# sch_microcontroller.net
KiCad netlist of a schematic drawn in EasyEDA
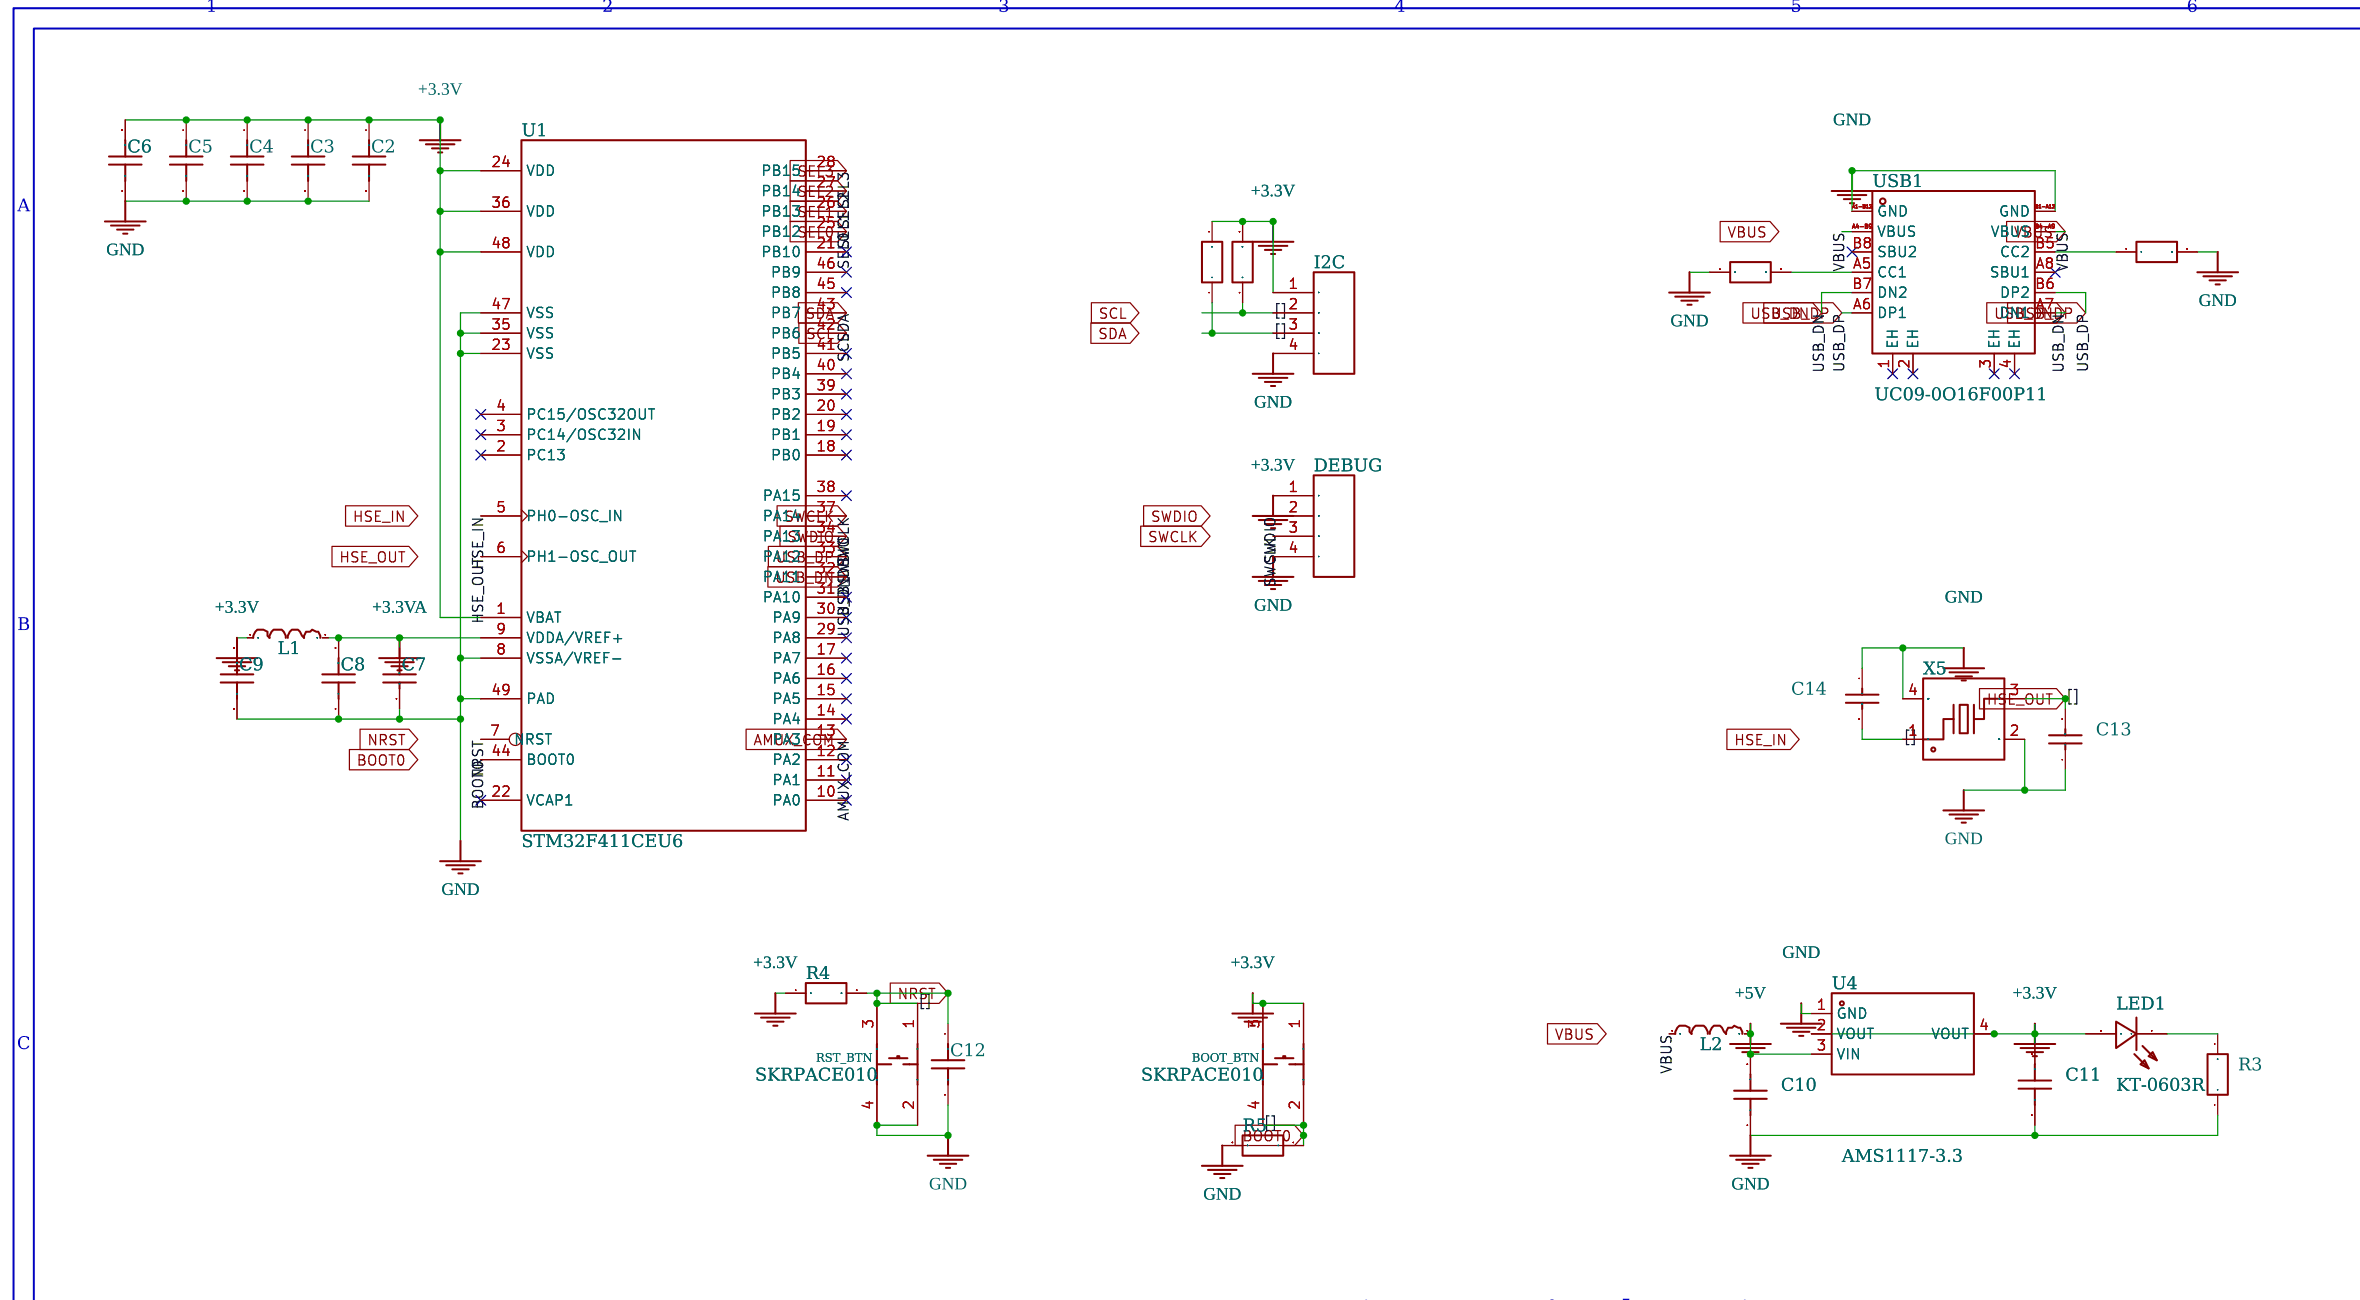
[diagram p0: schematic sheet]

(export (version "E")
  (design (tool "Eeschema 10.0.6"))
  (components
    (comp (ref "BOOT_BTN")
      (value "SKRPACE010")
      (fields (field (name "Manufacturer") "ALPSALPINE(阿尔卑斯阿尔派)"))
      (libsource (lib "") (part "Unknown_650_-325"))
    )
    (comp (ref "C2")
      (value "100nF")
      (fields
        (field (name "Manufacturer Part") "TCC0201X7R104K160ZT")
        (field (name "Manufacturer") "CCTC(三环)")
      )
      (libsource (lib "") (part "Unknown_195_-770"))
    )
    (comp (ref "C3")
      (value "100nF")
      (fields
        (field (name "Manufacturer Part") "TCC0201X7R104K160ZT")
        (field (name "Manufacturer") "CCTC(三环)")
      )
      (libsource (lib "") (part "Unknown_165_-770"))
    )
    (comp (ref "C4")
      (value "100nF")
      (fields
        (field (name "Manufacturer Part") "TCC0201X7R104K160ZT")
        (field (name "Manufacturer") "CCTC(三环)")
      )
      (libsource (lib "") (part "Unknown_135_-770"))
    )
    (comp (ref "C5")
      (value "100nF")
      (fields
        (field (name "Manufacturer Part") "TCC0201X7R104K160ZT")
        (field (name "Manufacturer") "CCTC(三环)")
      )
      (libsource (lib "") (part "Unknown_105_-770"))
    )
    (comp (ref "C6")
      (value "10uF")
      (fields
        (field (name "Manufacturer Part") "HGC1206R7106K350NSPJ")
        (field (name "Manufacturer") "Chinocera(华瓷)")
      )
      (libsource (lib "") (part "Unknown_75_-770"))
    )
    (comp (ref "C7")
      (value "10nF")
      (fields (field (name "Manufacturer Part") "0402B103K500NT") (field (name "Manufacturer") "FH(风华)"))
      (libsource (lib "") (part "Unknown_210_-515"))
    )
    (comp (ref "C8")
      (value "1uF")
      (fields
        (field (name "Manufacturer Part") "TCC0402X5R105K500AT")
        (field (name "Manufacturer") "CCTC(三环)")
      )
      (libsource (lib "") (part "Unknown_180_-515"))
    )
    (comp (ref "C9")
      (value "1uF")
      (fields
        (field (name "Manufacturer Part") "TCC0402X5R105K500AT")
        (field (name "Manufacturer") "CCTC(三环)")
      )
      (libsource (lib "") (part "Unknown_130_-515"))
    )
    (comp (ref "C10")
      (value "22uF")
      (fields
        (field (name "Manufacturer Part") "TCC1206X7R226K160HT")
        (field (name "Manufacturer") "CCTC(三环)")
      )
      (libsource (lib "") (part "Unknown_875_-310"))
    )
    (comp (ref "C11")
      (value "22uF")
      (fields
        (field (name "Manufacturer Part") "TCC1206X7R226K160HT")
        (field (name "Manufacturer") "CCTC(三环)")
      )
      (libsource (lib "") (part "Unknown_1015_-315"))
    )
    (comp (ref "C12")
      (value "100nF")
      (fields
        (field (name "Manufacturer Part") "TCC0201X7R104K160ZT")
        (field (name "Manufacturer") "CCTC(三环)")
      )
      (libsource (lib "") (part "Unknown_480_-325"))
    )
    (comp (ref "C13")
      (value "20pF")
      (fields (field (name "Manufacturer Part") "0402CG200J500NT") (field (name "Manufacturer") "FH(风华)"))
      (libsource (lib "") (part "Unknown_1030_-485"))
    )
    (comp (ref "C14")
      (value "20pF")
      (fields (field (name "Manufacturer Part") "0402CG200J500NT") (field (name "Manufacturer") "FH(风华)"))
      (libsource (lib "") (part "Unknown_930_-505"))
    )
    (comp (ref "DEBUG") (value "NO") (libsource (lib "") (part "Unknown_640_-595")))
    (comp (ref "I2C") (value "NO") (libsource (lib "") (part "Unknown_640_-695")))
    (comp (ref "L1")
      (value "BLM18AG121SN1D")
      (fields (field (name "Manufacturer") "muRata(村田)"))
      (libsource (lib "") (part "Unknown_155_-535"))
    )
    (comp (ref "L2")
      (value "BLM18AG121SN1D")
      (fields (field (name "Manufacturer") "muRata(村田)"))
      (libsource (lib "") (part "Unknown_855_-340"))
    )
    (comp (ref "LED1")
      (value "KT-0603R")
      (fields (field (name "Manufacturer") "KENTO"))
      (libsource (lib "") (part "Unknown_1060_-340"))
    )
    (comp (ref "R1")
      (value "5.1kΩ")
      (fields (field (name "Manufacturer Part") "FRC0402J512 TS") (field (name "Manufacturer") "FOJAN(富捷)"))
      (libsource (lib "") (part "Unknown_875_-715"))
    )
    (comp (ref "R2")
      (value "5.1kΩ")
      (fields (field (name "Manufacturer Part") "FRC0402J512 TS") (field (name "Manufacturer") "FOJAN(富捷)"))
      (libsource (lib "") (part "Unknown_1075_-725"))
    )
    (comp (ref "R3")
      (value "5.1kΩ")
      (fields (field (name "Manufacturer Part") "FRC0402J512 TS") (field (name "Manufacturer") "FOJAN(富捷)"))
      (libsource (lib "") (part "Unknown_1105_-320"))
    )
    (comp (ref "R4")
      (value "10kΩ")
      (fields
        (field (name "Manufacturer Part") "HoAR0805-1/8W-10KR-1%-TCR25")
        (field (name "Manufacturer") "Milliohm(毫欧)")
      )
      (libsource (lib "") (part "Unknown_420_-360"))
    )
    (comp (ref "R5")
      (value "10kΩ")
      (fields
        (field (name "Manufacturer Part") "HoAR0805-1/8W-10KR-1%-TCR25")
        (field (name "Manufacturer") "Milliohm(毫欧)")
      )
      (libsource (lib "") (part "Unknown_635_-285"))
    )
    (comp (ref "R6")
      (value "1.2kΩ")
      (fields (field (name "Manufacturer Part") "AC0201FR-071K2L") (field (name "Manufacturer") "YAGEO(国巨)"))
      (libsource (lib "") (part "Unknown_625_-720"))
    )
    (comp (ref "R7")
      (value "1.2kΩ")
      (fields (field (name "Manufacturer Part") "AC0201FR-071K2L") (field (name "Manufacturer") "YAGEO(国巨)"))
      (libsource (lib "") (part "Unknown_610_-720"))
    )
    (comp (ref "RST_BTN")
      (value "SKRPACE010")
      (fields (field (name "Manufacturer") "ALPSALPINE(阿尔卑斯阿尔派)"))
      (libsource (lib "") (part "Unknown_460_-325"))
    )
    (comp (ref "U1")
      (value "STM32F411CEU6")
      (fields (field (name "Manufacturer") "ST(意法半导体)"))
      (libsource (lib "") (part "Unknown_340_-605"))
    )
    (comp (ref "U4")
      (value "AMS1117-3.3")
      (fields (field (name "Manufacturer") "AMS"))
      (libsource (lib "") (part "Unknown_950_-340"))
    )
    (comp (ref "USB1")
      (value "UC09-0O16F00P11")
      (fields (field (name "Manufacturer") "BXCONN(宝讯)"))
      (libsource (lib "") (part "Unknown_975_-705"))
    )
    (comp (ref "X5")
      (value "25MHz")
      (fields (field (name "Manufacturer Part") "S3225000271060C3") (field (name "Manufacturer") "JGHC(晶光华)"))
      (libsource (lib "") (part "Unknown_980_-495"))
    )
  )
  (nets
    (net (code "1") (name "+3.3V") (class "Default")
      (node (ref "BOOT_BTN") (pin "1") (pinfunction "1_1") (pintype "unspecified"))
      (node (ref "BOOT_BTN") (pin "3") (pinfunction "3_3") (pintype "unspecified"))
      (node (ref "C11") (pin "2") (pinfunction "2_2") (pintype "unspecified"))
      (node (ref "C2") (pin "1") (pinfunction "1_1") (pintype "unspecified"))
      (node (ref "C3") (pin "1") (pinfunction "1_1") (pintype "unspecified"))
      (node (ref "C4") (pin "1") (pinfunction "1_1") (pintype "unspecified"))
      (node (ref "C5") (pin "1") (pinfunction "1_1") (pintype "unspecified"))
      (node (ref "C6") (pin "2") (pinfunction "2_2") (pintype "unspecified"))
      (node (ref "C9") (pin "2") (pinfunction "2_2") (pintype "unspecified"))
      (node (ref "DEBUG") (pin "1") (pinfunction "1_1") (pintype "unspecified"))
      (node (ref "I2C") (pin "1") (pinfunction "1_1") (pintype "unspecified"))
      (node (ref "L1") (pin "1") (pinfunction "1_1") (pintype "unspecified"))
      (node (ref "LED1") (pin "2") (pinfunction "A_2") (pintype "unspecified"))
      (node (ref "R4") (pin "1") (pinfunction "1_1") (pintype "unspecified"))
      (node (ref "R6") (pin "2") (pinfunction "2_2") (pintype "unspecified"))
      (node (ref "R7") (pin "2") (pinfunction "2_2") (pintype "unspecified"))
      (node (ref "U1") (pin "1") (pinfunction "VBAT_1") (pintype "unspecified"))
      (node (ref "U1") (pin "24") (pinfunction "VDD_24") (pintype "unspecified"))
      (node (ref "U1") (pin "36") (pinfunction "VDD_36") (pintype "unspecified"))
      (node (ref "U1") (pin "48") (pinfunction "VDD_48") (pintype "unspecified"))
      (node (ref "U4") (pin "2") (pinfunction "VOUT_2") (pintype "unspecified"))
      (node (ref "U4") (pin "4") (pinfunction "VOUT_4") (pintype "unspecified"))
    )
    (net (code "2") (name "+3.3VA") (class "Default")
      (node (ref "C7") (pin "2") (pinfunction "2_2") (pintype "unspecified"))
      (node (ref "C8") (pin "2") (pinfunction "2_2") (pintype "unspecified"))
      (node (ref "L1") (pin "2") (pinfunction "2_2") (pintype "unspecified"))
      (node (ref "U1") (pin "9") (pinfunction "VDDA/VREF+_9") (pintype "unspecified"))
    )
    (net (code "3") (name "+5V") (class "Default")
      (node (ref "C10") (pin "2") (pinfunction "2_2") (pintype "unspecified"))
      (node (ref "L2") (pin "2") (pinfunction "2_2") (pintype "unspecified"))
      (node (ref "U4") (pin "3") (pinfunction "VIN_3") (pintype "unspecified"))
    )
    (net (code "4") (name "AMUX_COM") (class "Default")
      (node (ref "U1") (pin "13") (pinfunction "PA3_13") (pintype "unspecified"))
    )
    (net (code "5") (name "BOOT0") (class "Default")
      (node (ref "BOOT_BTN") (pin "2") (pinfunction "2_2") (pintype "unspecified"))
      (node (ref "BOOT_BTN") (pin "4") (pinfunction "4_4") (pintype "unspecified"))
      (node (ref "C12") (pin "1") (pinfunction "1_1") (pintype "unspecified"))
      (node (ref "C13") (pin "2") (pinfunction "2_2") (pintype "unspecified"))
      (node (ref "C14") (pin "2") (pinfunction "2_2") (pintype "unspecified"))
      (node (ref "I2C") (pin "2") (pinfunction "2_2") (pintype "unspecified"))
      (node (ref "I2C") (pin "3") (pinfunction "3_3") (pintype "unspecified"))
      (node (ref "R4") (pin "2") (pinfunction "2_2") (pintype "unspecified"))
      (node (ref "R5") (pin "1") (pinfunction "1_1") (pintype "unspecified"))
      (node (ref "R6") (pin "1") (pinfunction "1_1") (pintype "unspecified"))
      (node (ref "R7") (pin "1") (pinfunction "1_1") (pintype "unspecified"))
      (node (ref "RST_BTN") (pin "1") (pinfunction "1_1") (pintype "unspecified"))
      (node (ref "RST_BTN") (pin "3") (pinfunction "3_3") (pintype "unspecified"))
      (node (ref "U1") (pin "44") (pinfunction "BOOT0_44") (pintype "unspecified"))
      (node (ref "U1") (pin "6") (pinfunction "PH1-OSC_OUT_6") (pintype "unspecified"))
      (node (ref "U1") (pin "7") (pinfunction "NRST_7") (pintype "unspecified"))
      (node (ref "X5") (pin "1") (pinfunction "1_1") (pintype "unspecified"))
      (node (ref "X5") (pin "3") (pinfunction "3_3") (pintype "unspecified"))
    )
    (net (code "6") (name "GND") (class "Default")
      (node (ref "C10") (pin "1") (pinfunction "1_1") (pintype "unspecified"))
      (node (ref "C11") (pin "1") (pinfunction "1_1") (pintype "unspecified"))
      (node (ref "C12") (pin "2") (pinfunction "2_2") (pintype "unspecified"))
      (node (ref "C13") (pin "1") (pinfunction "1_1") (pintype "unspecified"))
      (node (ref "C14") (pin "1") (pinfunction "1_1") (pintype "unspecified"))
      (node (ref "C2") (pin "2") (pinfunction "2_2") (pintype "unspecified"))
      (node (ref "C3") (pin "2") (pinfunction "2_2") (pintype "unspecified"))
      (node (ref "C4") (pin "2") (pinfunction "2_2") (pintype "unspecified"))
      (node (ref "C5") (pin "2") (pinfunction "2_2") (pintype "unspecified"))
      (node (ref "C6") (pin "1") (pinfunction "1_1") (pintype "unspecified"))
      (node (ref "C7") (pin "1") (pinfunction "1_1") (pintype "unspecified"))
      (node (ref "C8") (pin "1") (pinfunction "1_1") (pintype "unspecified"))
      (node (ref "C9") (pin "1") (pinfunction "1_1") (pintype "unspecified"))
      (node (ref "DEBUG") (pin "4") (pinfunction "4_4") (pintype "unspecified"))
      (node (ref "I2C") (pin "4") (pinfunction "4_4") (pintype "unspecified"))
      (node (ref "R1") (pin "1") (pinfunction "1_1") (pintype "unspecified"))
      (node (ref "R2") (pin "2") (pinfunction "2_2") (pintype "unspecified"))
      (node (ref "R3") (pin "1") (pinfunction "1_1") (pintype "unspecified"))
      (node (ref "R5") (pin "2") (pinfunction "2_2") (pintype "unspecified"))
      (node (ref "RST_BTN") (pin "2") (pinfunction "2_2") (pintype "unspecified"))
      (node (ref "RST_BTN") (pin "4") (pinfunction "4_4") (pintype "unspecified"))
      (node (ref "U1") (pin "23") (pinfunction "VSS_23") (pintype "unspecified"))
      (node (ref "U1") (pin "35") (pinfunction "VSS_35") (pintype "unspecified"))
      (node (ref "U1") (pin "47") (pinfunction "VSS_47") (pintype "unspecified"))
      (node (ref "U1") (pin "49") (pinfunction "PAD_49") (pintype "unspecified"))
      (node (ref "U1") (pin "8") (pinfunction "VSSA/VREF-_8") (pintype "unspecified"))
      (node (ref "U4") (pin "1") (pinfunction "GND_1") (pintype "unspecified"))
      (node (ref "USB1") (pin "A1-B12") (pinfunction "GND_A1-B12") (pintype "unspecified"))
      (node (ref "USB1") (pin "B1-A12") (pinfunction "GND_B1-A12") (pintype "unspecified"))
      (node (ref "X5") (pin "2") (pinfunction "GND_2") (pintype "unspecified"))
      (node (ref "X5") (pin "4") (pinfunction "GND_4") (pintype "unspecified"))
    )
    (net (code "7") (name "HSE_IN") (class "Default")
      (node (ref "U1") (pin "5") (pinfunction "PH0-OSC_IN_5") (pintype "unspecified"))
    )
    (net (code "8") (name "Net-(LED1-K)") (class "Default")
      (node (ref "LED1") (pin "1") (pinfunction "K_1") (pintype "unspecified"))
      (node (ref "R3") (pin "2") (pinfunction "2_2") (pintype "unspecified"))
    )
    (net (code "9") (name "Net-(USB1-CC1)") (class "Default")
      (node (ref "R1") (pin "2") (pinfunction "2_2") (pintype "unspecified"))
      (node (ref "USB1") (pin "A5") (pinfunction "CC1_A5") (pintype "unspecified"))
    )
    (net (code "10") (name "Net-(USB1-CC2)") (class "Default")
      (node (ref "R2") (pin "1") (pinfunction "1_1") (pintype "unspecified"))
      (node (ref "USB1") (pin "B5") (pinfunction "CC2_B5") (pintype "unspecified"))
    )
    (net (code "11") (name "SCL") (class "Default")
      (node (ref "U1") (pin "42") (pinfunction "PB6_42") (pintype "unspecified"))
    )
    (net (code "12") (name "SDA") (class "Default")
      (node (ref "U1") (pin "43") (pinfunction "PB7_43") (pintype "unspecified"))
    )
    (net (code "13") (name "SEL0") (class "Default")
      (node (ref "U1") (pin "25") (pinfunction "PB12_25") (pintype "unspecified"))
    )
    (net (code "14") (name "SEL1") (class "Default")
      (node (ref "U1") (pin "26") (pinfunction "PB13_26") (pintype "unspecified"))
    )
    (net (code "15") (name "SEL2") (class "Default")
      (node (ref "U1") (pin "27") (pinfunction "PB14_27") (pintype "unspecified"))
    )
    (net (code "16") (name "SEL3") (class "Default")
      (node (ref "U1") (pin "28") (pinfunction "PB15_28") (pintype "unspecified"))
    )
    (net (code "17") (name "SWCLK") (class "Default")
      (node (ref "DEBUG") (pin "3") (pinfunction "3_3") (pintype "unspecified"))
      (node (ref "U1") (pin "37") (pinfunction "PA14_37") (pintype "unspecified"))
    )
    (net (code "18") (name "SWDIO") (class "Default")
      (node (ref "DEBUG") (pin "2") (pinfunction "2_2") (pintype "unspecified"))
      (node (ref "U1") (pin "34") (pinfunction "PA13_34") (pintype "unspecified"))
    )
    (net (code "19") (name "USB_DN") (class "Default")
      (node (ref "U1") (pin "32") (pinfunction "PA11_32") (pintype "unspecified"))
      (node (ref "USB1") (pin "A7") (pinfunction "DN1_A7") (pintype "unspecified"))
      (node (ref "USB1") (pin "B7") (pinfunction "DN2_B7") (pintype "unspecified"))
    )
    (net (code "20") (name "USB_DP") (class "Default")
      (node (ref "U1") (pin "33") (pinfunction "PA12_33") (pintype "unspecified"))
      (node (ref "USB1") (pin "A6") (pinfunction "DP1_A6") (pintype "unspecified"))
      (node (ref "USB1") (pin "B6") (pinfunction "DP2_B6") (pintype "unspecified"))
    )
    (net (code "21") (name "VBUS") (class "Default")
      (node (ref "L2") (pin "1") (pinfunction "1_1") (pintype "unspecified"))
      (node (ref "USB1") (pin "A4-B9") (pinfunction "VBUS_A4-B9") (pintype "unspecified"))
      (node (ref "USB1") (pin "B4-A9") (pinfunction "VBUS_B4-A9") (pintype "unspecified"))
    )
    (net (code "22") (name "unconnected-(U1-PA0-Pad10)") (class "Default")
      (node (ref "U1") (pin "10") (pinfunction "PA0_10") (pintype "unspecified+no_connect"))
    )
    (net (code "23") (name "unconnected-(U1-PA1-Pad11)") (class "Default")
      (node (ref "U1") (pin "11") (pinfunction "PA1_11") (pintype "unspecified+no_connect"))
    )
    (net (code "24") (name "unconnected-(U1-PA2-Pad12)") (class "Default")
      (node (ref "U1") (pin "12") (pinfunction "PA2_12") (pintype "unspecified+no_connect"))
    )
    (net (code "25") (name "unconnected-(U1-PA4-Pad14)") (class "Default")
      (node (ref "U1") (pin "14") (pinfunction "PA4_14") (pintype "unspecified+no_connect"))
    )
    (net (code "26") (name "unconnected-(U1-PA5-Pad15)") (class "Default")
      (node (ref "U1") (pin "15") (pinfunction "PA5_15") (pintype "unspecified+no_connect"))
    )
    (net (code "27") (name "unconnected-(U1-PA6-Pad16)") (class "Default")
      (node (ref "U1") (pin "16") (pinfunction "PA6_16") (pintype "unspecified+no_connect"))
    )
    (net (code "28") (name "unconnected-(U1-PA7-Pad17)") (class "Default")
      (node (ref "U1") (pin "17") (pinfunction "PA7_17") (pintype "unspecified+no_connect"))
    )
    (net (code "29") (name "unconnected-(U1-PA8-Pad29)") (class "Default")
      (node (ref "U1") (pin "29") (pinfunction "PA8_29") (pintype "unspecified+no_connect"))
    )
    (net (code "30") (name "unconnected-(U1-PA9-Pad30)") (class "Default")
      (node (ref "U1") (pin "30") (pinfunction "PA9_30") (pintype "unspecified+no_connect"))
    )
    (net (code "31") (name "unconnected-(U1-PA10-Pad31)") (class "Default")
      (node (ref "U1") (pin "31") (pinfunction "PA10_31") (pintype "unspecified+no_connect"))
    )
    (net (code "32") (name "unconnected-(U1-PA15-Pad38)") (class "Default")
      (node (ref "U1") (pin "38") (pinfunction "PA15_38") (pintype "unspecified+no_connect"))
    )
    (net (code "33") (name "unconnected-(U1-PB0-Pad18)") (class "Default")
      (node (ref "U1") (pin "18") (pinfunction "PB0_18") (pintype "unspecified+no_connect"))
    )
    (net (code "34") (name "unconnected-(U1-PB1-Pad19)") (class "Default")
      (node (ref "U1") (pin "19") (pinfunction "PB1_19") (pintype "unspecified+no_connect"))
    )
    (net (code "35") (name "unconnected-(U1-PB2-Pad20)") (class "Default")
      (node (ref "U1") (pin "20") (pinfunction "PB2_20") (pintype "unspecified+no_connect"))
    )
    (net (code "36") (name "unconnected-(U1-PB3-Pad39)") (class "Default")
      (node (ref "U1") (pin "39") (pinfunction "PB3_39") (pintype "unspecified+no_connect"))
    )
    (net (code "37") (name "unconnected-(U1-PB4-Pad40)") (class "Default")
      (node (ref "U1") (pin "40") (pinfunction "PB4_40") (pintype "unspecified+no_connect"))
    )
    (net (code "38") (name "unconnected-(U1-PB5-Pad41)") (class "Default")
      (node (ref "U1") (pin "41") (pinfunction "PB5_41") (pintype "unspecified+no_connect"))
    )
    (net (code "39") (name "unconnected-(U1-PB8-Pad45)") (class "Default")
      (node (ref "U1") (pin "45") (pinfunction "PB8_45") (pintype "unspecified+no_connect"))
    )
    (net (code "40") (name "unconnected-(U1-PB9-Pad46)") (class "Default")
      (node (ref "U1") (pin "46") (pinfunction "PB9_46") (pintype "unspecified+no_connect"))
    )
    (net (code "41") (name "unconnected-(U1-PB10-Pad21)") (class "Default")
      (node (ref "U1") (pin "21") (pinfunction "PB10_21") (pintype "unspecified+no_connect"))
    )
    (net (code "42") (name "unconnected-(U1-PC13-Pad2)") (class "Default")
      (node (ref "U1") (pin "2") (pinfunction "PC13_2") (pintype "unspecified+no_connect"))
    )
    (net (code "43") (name "unconnected-(U1-PC14{slash}OSC32IN-Pad3)") (class "Default")
      (node (ref "U1") (pin "3") (pinfunction "PC14/OSC32IN_3") (pintype "unspecified+no_connect"))
    )
    (net (code "44") (name "unconnected-(U1-PC15{slash}OSC32OUT-Pad4)") (class "Default")
      (node (ref "U1") (pin "4") (pinfunction "PC15/OSC32OUT_4") (pintype "unspecified+no_connect"))
    )
    (net (code "45") (name "unconnected-(U1-VCAP1-Pad22)") (class "Default")
      (node (ref "U1") (pin "22") (pinfunction "VCAP1_22") (pintype "unspecified+no_connect"))
    )
    (net (code "46") (name "unconnected-(USB1-EH-Pad1)") (class "Default")
      (node (ref "USB1") (pin "1") (pinfunction "EH_1") (pintype "unspecified+no_connect"))
    )
    (net (code "47") (name "unconnected-(USB1-EH-Pad2)") (class "Default")
      (node (ref "USB1") (pin "2") (pinfunction "EH_2") (pintype "unspecified+no_connect"))
    )
    (net (code "48") (name "unconnected-(USB1-EH-Pad3)") (class "Default")
      (node (ref "USB1") (pin "3") (pinfunction "EH_3") (pintype "unspecified+no_connect"))
    )
    (net (code "49") (name "unconnected-(USB1-EH-Pad4)") (class "Default")
      (node (ref "USB1") (pin "4") (pinfunction "EH_4") (pintype "unspecified+no_connect"))
    )
    (net (code "50") (name "unconnected-(USB1-SBU1-PadA8)") (class "Default")
      (node (ref "USB1") (pin "A8") (pinfunction "SBU1_A8") (pintype "unspecified+no_connect"))
    )
    (net (code "51") (name "unconnected-(USB1-SBU2-PadB8)") (class "Default")
      (node (ref "USB1") (pin "B8") (pinfunction "SBU2_B8") (pintype "unspecified+no_connect"))
    )
  )
)
